# T-FC10W-M.net
KiCad netlist of a schematic drawn in Altium Designer
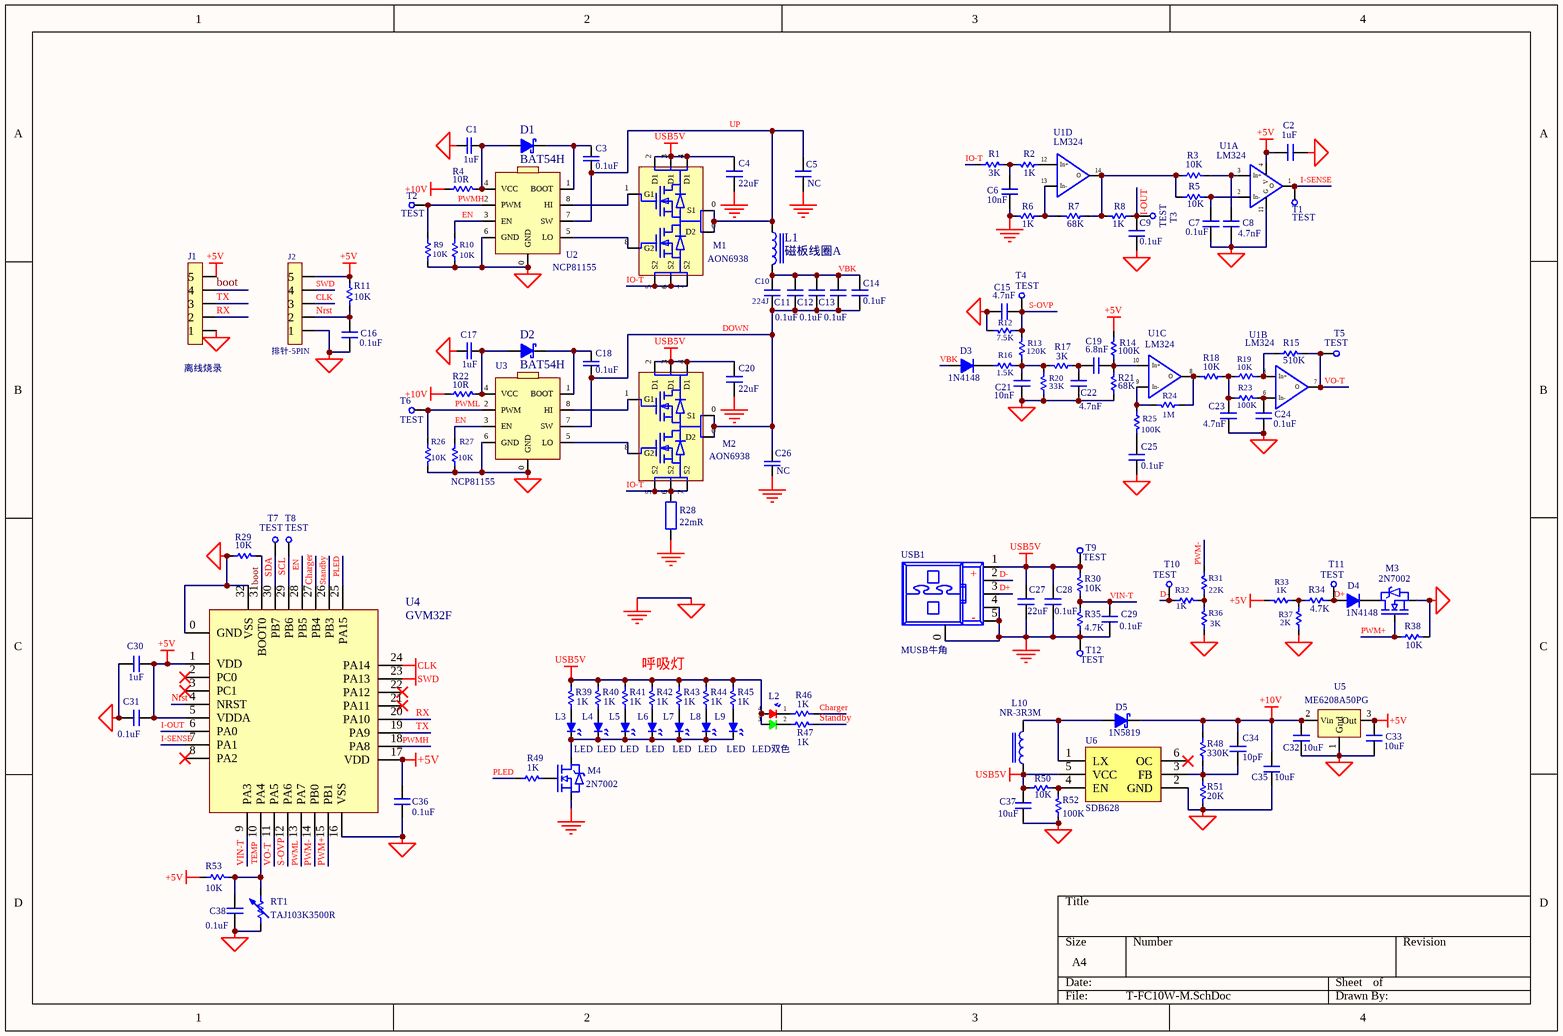
[diagram p0: T-FC10W-M.SchDoc]

(export (version "E")
  (design (tool "Eeschema 10.0.6"))
  (components
    (comp (ref "C1")
      (value "0.1uF")
      (footprint "0603")
      (description "16V")
      (fields (field (name "ALTIUM_UNNAMED_1") "1uF"))
      (libsource (lib "") (part "C0603_1"))
    )
    (comp (ref "C2")
      (value "1uF")
      (footprint "0603")
      (description "16V")
      (libsource (lib "我的元件集成库") (part "C0603"))
    )
    (comp (ref "C3")
      (value "0.1uF")
      (footprint "0603")
      (description "16V")
      (fields (field (name "ALTIUM_UNNAMED_1") "0.1uF"))
      (libsource (lib "") (part "C0603_1"))
    )
    (comp (ref "C4")
      (value "22uF")
      (footprint "1206")
      (description "16V")
      (libsource (lib "我的元件集成库") (part "C1206A"))
    )
    (comp (ref "C5")
      (value "NC")
      (footprint "0603")
      (description "16V")
      (libsource (lib "我的元件集成库") (part "C0603"))
    )
    (comp (ref "C6")
      (value "10nF")
      (footprint "0603")
      (description "16V")
      (libsource (lib "我的元件集成库") (part "C0603"))
    )
    (comp (ref "C7")
      (value "0.1uF")
      (footprint "0603")
      (description "16V")
      (libsource (lib "我的元件集成库") (part "C0603"))
    )
    (comp (ref "C8")
      (value "4.7nF")
      (footprint "0603")
      (description "16V")
      (libsource (lib "我的元件集成库") (part "C0603"))
    )
    (comp (ref "C9")
      (value "0.1uF")
      (footprint "0603")
      (description "16V")
      (libsource (lib "我的元件集成库") (part "C0603"))
    )
    (comp (ref "C10") (value "224J") (footprint "薄膜电容A") (libsource (lib "我的元件集成库") (part "薄膜电容B")))
    (comp (ref "C11")
      (value "0.1uF")
      (footprint "1206")
      (description "NPO")
      (libsource (lib "我的元件集成库") (part "C1206"))
    )
    (comp (ref "C12")
      (value "0.1uF")
      (footprint "1206")
      (description "NPO")
      (libsource (lib "我的元件集成库") (part "C1206"))
    )
    (comp (ref "C13")
      (value "0.1uF")
      (footprint "1206")
      (description "NPO")
      (libsource (lib "我的元件集成库") (part "C1206"))
    )
    (comp (ref "C14")
      (value "0.1uF")
      (footprint "1206")
      (description "NPO")
      (libsource (lib "我的元件集成库") (part "C1206"))
    )
    (comp (ref "C15")
      (value "4.7nF")
      (footprint "0603")
      (description "16V")
      (libsource (lib "我的元件集成库") (part "C0603"))
    )
    (comp (ref "C16")
      (value "0.1uF")
      (footprint "0603")
      (description "16V")
      (libsource (lib "我的元件集成库") (part "C0603"))
    )
    (comp (ref "C17")
      (value "0.1uF")
      (footprint "0603")
      (description "16V")
      (fields (field (name "ALTIUM_UNNAMED_1") "1uF"))
      (libsource (lib "") (part "C0603_1"))
    )
    (comp (ref "C18")
      (value "0.1uF")
      (footprint "0603")
      (description "16V")
      (fields (field (name "ALTIUM_UNNAMED_1") "0.1uF"))
      (libsource (lib "") (part "C0603_1"))
    )
    (comp (ref "C19")
      (value "6.8nF")
      (footprint "0603")
      (description "16V")
      (libsource (lib "我的元件集成库") (part "C0603"))
    )
    (comp (ref "C20")
      (value "22uF")
      (footprint "1206")
      (description "16V")
      (libsource (lib "我的元件集成库") (part "C1206A"))
    )
    (comp (ref "C21")
      (value "10nF")
      (footprint "0603")
      (description "16V")
      (libsource (lib "我的元件集成库") (part "C0603"))
    )
    (comp (ref "C22")
      (value "4.7nF")
      (footprint "0603")
      (description "16V")
      (libsource (lib "我的元件集成库") (part "C0603"))
    )
    (comp (ref "C23")
      (value "4.7nF")
      (footprint "0603")
      (description "16V")
      (libsource (lib "我的元件集成库") (part "C0603"))
    )
    (comp (ref "C24")
      (value "0.1uF")
      (footprint "0603")
      (description "16V")
      (libsource (lib "我的元件集成库") (part "C0603"))
    )
    (comp (ref "C25")
      (value "0.1uF")
      (footprint "0603")
      (description "16V")
      (libsource (lib "我的元件集成库") (part "C0603"))
    )
    (comp (ref "C26")
      (value "NC")
      (footprint "0603")
      (description "16V")
      (libsource (lib "") (part "C0603_1"))
    )
    (comp (ref "C27")
      (value "22uF")
      (footprint "1206")
      (description "16V")
      (libsource (lib "我的元件集成库") (part "C1206A"))
    )
    (comp (ref "C28")
      (value "0.1uF")
      (footprint "0603")
      (description "16V")
      (libsource (lib "我的元件集成库") (part "C0603"))
    )
    (comp (ref "C29")
      (value "0.1uF")
      (footprint "0603")
      (description "16V")
      (libsource (lib "我的元件集成库") (part "C0603"))
    )
    (comp (ref "C30")
      (value "1uF")
      (footprint "0603")
      (description "16V")
      (libsource (lib "我的元件集成库") (part "C0603"))
    )
    (comp (ref "C31")
      (value "0.1uF")
      (footprint "0603")
      (description "16V")
      (libsource (lib "我的元件集成库") (part "C0603"))
    )
    (comp (ref "C32")
      (value "10uF")
      (footprint "0805")
      (description "16V")
      (libsource (lib "我的元件集成库") (part "C0805"))
    )
    (comp (ref "C33")
      (value "10uF")
      (footprint "0805")
      (description "16V")
      (libsource (lib "我的元件集成库") (part "C0805"))
    )
    (comp (ref "C34")
      (value "10pF")
      (footprint "0603")
      (description "16V")
      (libsource (lib "我的元件集成库") (part "C0603"))
    )
    (comp (ref "C35")
      (value "10uF")
      (footprint "0805")
      (description "16V")
      (libsource (lib "我的元件集成库") (part "C0805"))
    )
    (comp (ref "C36")
      (value "0.1uF")
      (footprint "0603")
      (description "16V")
      (libsource (lib "我的元件集成库") (part "C0603"))
    )
    (comp (ref "C37")
      (value "10uF")
      (footprint "0805")
      (description "16V")
      (libsource (lib "我的元件集成库") (part "C0805"))
    )
    (comp (ref "C38")
      (value "0.1uF")
      (footprint "0603")
      (description "16V")
      (libsource (lib "我的元件集成库") (part "C0603"))
    )
    (comp (ref "D1") (value "BAT54H") (footprint "SOD-323") (libsource (lib "我的元件集成库") (part "DIODE-SOD323")))
    (comp (ref "D2") (value "BAT54H") (footprint "SOD-323") (libsource (lib "我的元件集成库") (part "DIODE-SOD323")))
    (comp (ref "D3")
      (value "1N4148")
      (footprint "SOD-323")
      (libsource (lib "我的元件集成库") (part "DIODE-SOD323A"))
    )
    (comp (ref "D4")
      (value "1N4148")
      (footprint "SOD-323")
      (libsource (lib "我的元件集成库") (part "DIODE-SOD323A"))
    )
    (comp (ref "D5") (value "1N5819") (footprint "SOD-123") (libsource (lib "我的元件集成库") (part "DIODE-SOD123")))
    (comp (ref "J1")
      (value "离线烧录")
      (footprint "5PIN排针1.25mm")
      (description "排针-5PIN")
      (libsource (lib "我的元件集成库") (part "排针-5PIN"))
    )
    (comp (ref "J2")
      (value "排针-5PIN")
      (footprint "5PIN排针1.25mm")
      (libsource (lib "我的元件集成库") (part "排针-5PIN"))
    )
    (comp (ref "L1") (value "磁板线圈A") (footprint "磁板线圈") (libsource (lib "我的元件集成库") (part "磁板线圈A")))
    (comp (ref "L2") (value "LED双色") (footprint "LED0603双色") (libsource (lib "我的元件集成库") (part "LED0603双色")))
    (comp (ref "L3")
      (value "LED")
      (footprint "LED0802")
      (description "LED0802侧发光")
      (libsource (lib "我的元件集成库") (part "LED0802"))
    )
    (comp (ref "L4")
      (value "LED")
      (footprint "LED0802")
      (description "LED0802侧发光")
      (libsource (lib "我的元件集成库") (part "LED0802"))
    )
    (comp (ref "L5")
      (value "LED")
      (footprint "LED0802")
      (description "LED0802侧发光")
      (libsource (lib "我的元件集成库") (part "LED0802"))
    )
    (comp (ref "L6")
      (value "LED")
      (footprint "LED0802")
      (description "LED0802侧发光")
      (libsource (lib "我的元件集成库") (part "LED0802"))
    )
    (comp (ref "L7")
      (value "LED")
      (footprint "LED0802")
      (description "LED0802侧发光")
      (libsource (lib "我的元件集成库") (part "LED0802"))
    )
    (comp (ref "L8")
      (value "LED")
      (footprint "LED0802")
      (description "LED0802侧发光")
      (libsource (lib "我的元件集成库") (part "LED0802"))
    )
    (comp (ref "L9")
      (value "LED")
      (footprint "LED0802")
      (description "LED0802侧发光")
      (libsource (lib "我的元件集成库") (part "LED0802"))
    )
    (comp (ref "L10") (value "NR-3R3M") (footprint "L3015T") (libsource (lib "我的元件集成库") (part "L3015")))
    (comp (ref "M1")
      (value "AON6938")
      (footprint "QFN-5*6")
      (description "MOS双N")
      (libsource (lib "我的元件集成库") (part "MOS-双N-DFN56"))
    )
    (comp (ref "M2")
      (value "AON6938")
      (footprint "QFN-5*6")
      (description "MOS双N")
      (libsource (lib "我的元件集成库") (part "MOS-双N-DFN56"))
    )
    (comp (ref "M3")
      (value "2N7002")
      (footprint "SOT-23-L")
      (libsource (lib "我的元件集成库") (part "MOS-N-SOT23A"))
    )
    (comp (ref "M4")
      (value "2N7002")
      (footprint "SOT-23-L")
      (libsource (lib "我的元件集成库") (part "MOS-N-SOT23A"))
    )
    (comp (ref "R1")
      (value "3K")
      (footprint "0603")
      (description "5%")
      (libsource (lib "我的元件集成库") (part "R0603"))
    )
    (comp (ref "R2")
      (value "1K")
      (footprint "0603")
      (description "1%")
      (libsource (lib "我的元件集成库") (part "R0603A"))
    )
    (comp (ref "R3")
      (value "10K")
      (footprint "0603")
      (description "1%")
      (libsource (lib "我的元件集成库") (part "R0603A"))
    )
    (comp (ref "R4")
      (value "10R")
      (footprint "0603")
      (description "5%")
      (libsource (lib "") (part "R0603_1"))
    )
    (comp (ref "R5")
      (value "10K")
      (footprint "0603")
      (description "1%")
      (libsource (lib "我的元件集成库") (part "R0603A"))
    )
    (comp (ref "R6")
      (value "1K")
      (footprint "0603")
      (description "1%")
      (libsource (lib "我的元件集成库") (part "R0603A"))
    )
    (comp (ref "R7")
      (value "68K")
      (footprint "0603")
      (description "1%")
      (libsource (lib "我的元件集成库") (part "R0603A"))
    )
    (comp (ref "R8")
      (value "1K")
      (footprint "0603")
      (description "5%")
      (libsource (lib "我的元件集成库") (part "R0603"))
    )
    (comp (ref "R9")
      (value "10K")
      (footprint "0603")
      (description "5%")
      (libsource (lib "我的元件集成库") (part "R0603"))
    )
    (comp (ref "R10")
      (value "10K")
      (footprint "0603")
      (description "5%")
      (libsource (lib "我的元件集成库") (part "R0603"))
    )
    (comp (ref "R11")
      (value "10K")
      (footprint "0603")
      (description "5%")
      (libsource (lib "我的元件集成库") (part "R0603"))
    )
    (comp (ref "R12")
      (value "7.5K")
      (footprint "0603")
      (description "1%")
      (libsource (lib "我的元件集成库") (part "R0603A"))
    )
    (comp (ref "R13")
      (value "120K")
      (footprint "0603")
      (description "1%")
      (libsource (lib "我的元件集成库") (part "R0603A"))
    )
    (comp (ref "R14")
      (value "100K")
      (footprint "0603")
      (description "1%")
      (libsource (lib "我的元件集成库") (part "R0603A"))
    )
    (comp (ref "R15")
      (value "510K")
      (footprint "0603")
      (description "5%")
      (libsource (lib "我的元件集成库") (part "R0603"))
    )
    (comp (ref "R16")
      (value "1.5K")
      (footprint "0603")
      (description "1%")
      (libsource (lib "我的元件集成库") (part "R0603A"))
    )
    (comp (ref "R17")
      (value "3K")
      (footprint "0603")
      (description "5%")
      (libsource (lib "我的元件集成库") (part "R0603"))
    )
    (comp (ref "R18")
      (value "10K")
      (footprint "0603")
      (description "5%")
      (libsource (lib "我的元件集成库") (part "R0603"))
    )
    (comp (ref "R19")
      (value "10K")
      (footprint "0603")
      (description "1%")
      (libsource (lib "我的元件集成库") (part "R0603A"))
    )
    (comp (ref "R20")
      (value "33K")
      (footprint "0603")
      (description "1%")
      (libsource (lib "我的元件集成库") (part "R0603A"))
    )
    (comp (ref "R21")
      (value "68K")
      (footprint "0603")
      (description "1%")
      (libsource (lib "我的元件集成库") (part "R0603A"))
    )
    (comp (ref "R22")
      (value "10R")
      (footprint "0603")
      (description "5%")
      (libsource (lib "") (part "R0603_1"))
    )
    (comp (ref "R23")
      (value "100K")
      (footprint "0603")
      (description "1%")
      (libsource (lib "我的元件集成库") (part "R0603A"))
    )
    (comp (ref "R24")
      (value "1M")
      (footprint "0603")
      (description "1%")
      (libsource (lib "我的元件集成库") (part "R0603A"))
    )
    (comp (ref "R25")
      (value "100K")
      (footprint "0603")
      (description "1%")
      (libsource (lib "我的元件集成库") (part "R0603A"))
    )
    (comp (ref "R26")
      (value "10K")
      (footprint "0603")
      (description "5%")
      (libsource (lib "我的元件集成库") (part "R0603"))
    )
    (comp (ref "R27")
      (value "10K")
      (footprint "0603")
      (description "5%")
      (libsource (lib "我的元件集成库") (part "R0603"))
    )
    (comp (ref "R28")
      (value "22mR")
      (footprint "1206")
      (description "5%")
      (libsource (lib "我的元件集成库") (part "R1206"))
    )
    (comp (ref "R29")
      (value "10K")
      (footprint "0603")
      (description "5%")
      (libsource (lib "我的元件集成库") (part "R0603"))
    )
    (comp (ref "R30")
      (value "10K")
      (footprint "0603")
      (description "1%")
      (libsource (lib "我的元件集成库") (part "R0603A"))
    )
    (comp (ref "R31")
      (value "22K")
      (footprint "0603")
      (description "1%")
      (libsource (lib "我的元件集成库") (part "R0603A"))
    )
    (comp (ref "R32")
      (value "1K")
      (footprint "0603")
      (description "5%")
      (libsource (lib "我的元件集成库") (part "R0603"))
    )
    (comp (ref "R33")
      (value "1K")
      (footprint "0603")
      (description "1%")
      (libsource (lib "我的元件集成库") (part "R0603A"))
    )
    (comp (ref "R34")
      (value "4.7K")
      (footprint "0603")
      (description "5%")
      (libsource (lib "我的元件集成库") (part "R0603"))
    )
    (comp (ref "R35")
      (value "4.7K")
      (footprint "0603")
      (description "1%")
      (libsource (lib "我的元件集成库") (part "R0603A"))
    )
    (comp (ref "R36")
      (value "3K")
      (footprint "0603")
      (description "1%")
      (libsource (lib "我的元件集成库") (part "R0603A"))
    )
    (comp (ref "R37")
      (value "2K")
      (footprint "0603")
      (description "1%")
      (libsource (lib "我的元件集成库") (part "R0603A"))
    )
    (comp (ref "R38")
      (value "10K")
      (footprint "0603")
      (description "5%")
      (libsource (lib "我的元件集成库") (part "R0603"))
    )
    (comp (ref "R39")
      (value "1K")
      (footprint "0603")
      (description "5%")
      (libsource (lib "我的元件集成库") (part "R0603"))
    )
    (comp (ref "R40")
      (value "1K")
      (footprint "0603")
      (description "5%")
      (libsource (lib "我的元件集成库") (part "R0603"))
    )
    (comp (ref "R41")
      (value "1K")
      (footprint "0603")
      (description "5%")
      (libsource (lib "我的元件集成库") (part "R0603"))
    )
    (comp (ref "R42")
      (value "1K")
      (footprint "0603")
      (description "5%")
      (libsource (lib "我的元件集成库") (part "R0603"))
    )
    (comp (ref "R43")
      (value "1K")
      (footprint "0603")
      (description "5%")
      (libsource (lib "我的元件集成库") (part "R0603"))
    )
    (comp (ref "R44")
      (value "1K")
      (footprint "0603")
      (description "5%")
      (libsource (lib "我的元件集成库") (part "R0603"))
    )
    (comp (ref "R45")
      (value "1K")
      (footprint "0603")
      (description "5%")
      (libsource (lib "我的元件集成库") (part "R0603"))
    )
    (comp (ref "R46")
      (value "1K")
      (footprint "0603")
      (description "5%")
      (libsource (lib "我的元件集成库") (part "R0603"))
    )
    (comp (ref "R47")
      (value "1K")
      (footprint "0603")
      (description "5%")
      (libsource (lib "我的元件集成库") (part "R0603"))
    )
    (comp (ref "R48")
      (value "330K")
      (footprint "0603")
      (description "1%")
      (libsource (lib "我的元件集成库") (part "R0603A"))
    )
    (comp (ref "R49")
      (value "1K")
      (footprint "0603")
      (description "5%")
      (libsource (lib "我的元件集成库") (part "R0603"))
    )
    (comp (ref "R50")
      (value "10K")
      (footprint "0603")
      (description "5%")
      (libsource (lib "我的元件集成库") (part "R0603"))
    )
    (comp (ref "R51")
      (value "20K")
      (footprint "0603")
      (description "1%")
      (libsource (lib "我的元件集成库") (part "R0603A"))
    )
    (comp (ref "R52")
      (value "100K")
      (footprint "0603")
      (description "5%")
      (libsource (lib "我的元件集成库") (part "R0603"))
    )
    (comp (ref "R53")
      (value "10K")
      (footprint "0603")
      (description "5%")
      (libsource (lib "我的元件集成库") (part "R0603"))
    )
    (comp (ref "RT1")
      (value "TAJ103K3500R")
      (footprint "0603")
      (description "5%")
      (libsource (lib "我的元件集成库") (part "R0603-ADJ"))
    )
    (comp (ref "T1") (value "TEST") (footprint "测试点") (libsource (lib "我的元件集成库") (part "TEST-PIONT")))
    (comp (ref "T2") (value "TEST") (footprint "测试点") (libsource (lib "我的元件集成库") (part "TEST-PIONT")))
    (comp (ref "T3") (value "TEST") (footprint "测试点") (libsource (lib "我的元件集成库") (part "TEST-PIONT")))
    (comp (ref "T4") (value "TEST") (footprint "测试点") (libsource (lib "我的元件集成库") (part "TEST-PIONT")))
    (comp (ref "T5") (value "TEST") (footprint "测试点") (libsource (lib "我的元件集成库") (part "TEST-PIONT")))
    (comp (ref "T6") (value "TEST") (footprint "测试点") (libsource (lib "我的元件集成库") (part "TEST-PIONT")))
    (comp (ref "T7") (value "TEST") (footprint "测试点") (libsource (lib "我的元件集成库") (part "TEST-PIONT")))
    (comp (ref "T8") (value "TEST") (footprint "测试点") (libsource (lib "我的元件集成库") (part "TEST-PIONT")))
    (comp (ref "T9") (value "TEST") (footprint "测试点") (libsource (lib "我的元件集成库") (part "TEST-PIONT")))
    (comp (ref "T10") (value "TEST") (footprint "测试点") (libsource (lib "我的元件集成库") (part "TEST-PIONT")))
    (comp (ref "T11") (value "TEST") (footprint "测试点") (libsource (lib "我的元件集成库") (part "TEST-PIONT")))
    (comp (ref "T12") (value "TEST") (footprint "测试点") (libsource (lib "我的元件集成库") (part "TEST-PIONT")))
    (comp (ref "U1") (value "LM324") (footprint "SOP-14") (libsource (lib "我的元件集成库") (part "IC-SOP-14")))
    (comp (ref "U2") (value "NCP81155") (footprint "QFN-3*3-1") (libsource (lib "我的元件集成库") (part "IC-QFN33")))
    (comp (ref "U3") (value "NCP81155") (footprint "QFN-3*3-1") (libsource (lib "我的元件集成库") (part "IC-QFN33")))
    (comp (ref "U4") (value "GVM32F") (footprint "QFN-32PIN") (libsource (lib "我的元件集成库") (part "IC-QFN32PA")))
    (comp (ref "U5")
      (value "ME6208A50PG")
      (footprint "SOT-89")
      (libsource (lib "我的元件集成库") (part "LDO-SOT89"))
    )
    (comp (ref "U6") (value "SDB628") (footprint "SOT-23-6") (libsource (lib "我的元件集成库") (part "IC-SOT23-6")))
    (comp (ref "USB1")
      (value "MUSB牛角")
      (footprint "MICRO-USB牛角")
      (libsource (lib "我的元件集成库") (part "MICRO-USB-牛角"))
    )
  )
  (nets
    (net (code "1") (name "+5V") (class "Default")
      (node (ref "C2") (pin "2") (pinfunction "2_2") (pintype "passive"))
      (node (ref "C30") (pin "1") (pinfunction "1_1") (pintype "passive"))
      (node (ref "C31") (pin "1") (pinfunction "1_1") (pintype "passive"))
      (node (ref "C33") (pin "2") (pinfunction "2_2") (pintype "passive"))
      (node (ref "C36") (pin "1") (pinfunction "1_1") (pintype "passive"))
      (node (ref "J1") (pin "5") (pinfunction "5_5") (pintype "passive"))
      (node (ref "J2") (pin "5") (pinfunction "5_5") (pintype "passive"))
      (node (ref "R11") (pin "1") (pinfunction "1_1") (pintype "passive"))
      (node (ref "R14") (pin "2") (pinfunction "2_2") (pintype "passive"))
      (node (ref "R33") (pin "2") (pinfunction "2_2") (pintype "passive"))
      (node (ref "R53") (pin "1") (pinfunction "1_1") (pintype "passive"))
      (node (ref "U1") (pin "4") (pinfunction "V_4") (pintype "passive"))
      (node (ref "U4") (pin "1") (pinfunction "VDD_1") (pintype "passive"))
      (node (ref "U4") (pin "17") (pinfunction "VDD_17") (pintype "passive"))
      (node (ref "U4") (pin "5") (pinfunction "VDDA_5") (pintype "passive"))
      (node (ref "U5") (pin "3") (pinfunction "Out_3") (pintype "passive"))
    )
    (net (code "2") (name "+10V") (class "Default")
      (node (ref "C32") (pin "2") (pinfunction "2_2") (pintype "passive"))
      (node (ref "C34") (pin "2") (pinfunction "2_2") (pintype "passive"))
      (node (ref "C35") (pin "2") (pinfunction "2_2") (pintype "passive"))
      (node (ref "D5") (pin "2") (pinfunction "K_2") (pintype "passive"))
      (node (ref "R22") (pin "1") (pinfunction "1_1") (pintype "passive"))
      (node (ref "R4") (pin "1") (pinfunction "1_1") (pintype "passive"))
      (node (ref "R48") (pin "2") (pinfunction "2_2") (pintype "passive"))
      (node (ref "U5") (pin "2") (pinfunction "Vin_2") (pintype "passive"))
    )
    (net (code "3") (name "/Charger") (class "Default")
      (node (ref "R46") (pin "2") (pinfunction "2_2") (pintype "passive"))
      (node (ref "U4") (pin "27") (pinfunction "PB4_27") (pintype "passive"))
    )
    (net (code "4") (name "/D+") (class "Default")
      (node (ref "D4") (pin "1") (pinfunction "1_1") (pintype "passive"))
      (node (ref "R34") (pin "2") (pinfunction "2_2") (pintype "passive"))
      (node (ref "T11") (pin "1") (pinfunction "1_1") (pintype "passive"))
      (node (ref "USB1") (pin "3") (pinfunction "3_3") (pintype "passive"))
    )
    (net (code "5") (name "/D-") (class "Default")
      (node (ref "R32") (pin "1") (pinfunction "1_1") (pintype "passive"))
      (node (ref "T10") (pin "1") (pinfunction "1_1") (pintype "passive"))
      (node (ref "USB1") (pin "2") (pinfunction "2_2") (pintype "passive"))
    )
    (net (code "6") (name "/DOWN") (class "Default")
      (node (ref "C10") (pin "1") (pinfunction "1_1") (pintype "passive"))
      (node (ref "C11") (pin "1") (pinfunction "1_1") (pintype "passive"))
      (node (ref "C12") (pin "1") (pinfunction "1_1") (pintype "passive"))
      (node (ref "C13") (pin "1") (pinfunction "1_1") (pintype "passive"))
      (node (ref "C14") (pin "1") (pinfunction "1_1") (pintype "passive"))
      (node (ref "C18") (pin "1") (pinfunction "1_1") (pintype "passive"))
      (node (ref "C26") (pin "2") (pinfunction "2_2") (pintype "passive"))
      (node (ref "M2") (pin "0") (pinfunction "S1_0") (pintype "passive"))
      (node (ref "U3") (pin "7") (pinfunction "SW_7") (pintype "passive"))
    )
    (net (code "7") (name "/EN") (class "Default")
      (node (ref "R10") (pin "2") (pinfunction "2_2") (pintype "passive"))
      (node (ref "R27") (pin "2") (pinfunction "2_2") (pintype "passive"))
      (node (ref "U2") (pin "3") (pinfunction "EN_3") (pintype "passive"))
      (node (ref "U3") (pin "3") (pinfunction "EN_3") (pintype "passive"))
      (node (ref "U4") (pin "28") (pinfunction "PB5_28") (pintype "passive"))
    )
    (net (code "8") (name "/I-OUT") (class "Default")
      (node (ref "C9") (pin "1") (pinfunction "1_1") (pintype "passive"))
      (node (ref "R8") (pin "1") (pinfunction "1_1") (pintype "passive"))
      (node (ref "T3") (pin "1") (pinfunction "1_1") (pintype "passive"))
      (node (ref "U4") (pin "6") (pinfunction "PA0_6") (pintype "passive"))
    )
    (net (code "9") (name "/I-SENSE") (class "Default")
      (node (ref "T1") (pin "1") (pinfunction "1_1") (pintype "passive"))
      (node (ref "U1") (pin "1") (pinfunction "O_1") (pintype "passive"))
      (node (ref "U4") (pin "7") (pinfunction "PA1_7") (pintype "passive"))
    )
    (net (code "10") (name "/IO-T") (class "Default")
      (node (ref "M1") (pin "5") (pinfunction "S2_5") (pintype "passive"))
      (node (ref "M1") (pin "6") (pinfunction "S2_6") (pintype "passive"))
      (node (ref "M1") (pin "7") (pinfunction "S2_7") (pintype "passive"))
      (node (ref "M2") (pin "5") (pinfunction "S2_5") (pintype "passive"))
      (node (ref "M2") (pin "6") (pinfunction "S2_6") (pintype "passive"))
      (node (ref "M2") (pin "7") (pinfunction "S2_7") (pintype "passive"))
      (node (ref "R1") (pin "1") (pinfunction "1_1") (pintype "passive"))
      (node (ref "R28") (pin "2") (pinfunction "2_2") (pintype "passive"))
    )
    (net (code "11") (name "/Nrst") (class "Default")
      (node (ref "C16") (pin "2") (pinfunction "2_2") (pintype "passive"))
      (node (ref "J2") (pin "2") (pinfunction "2_2") (pintype "passive"))
      (node (ref "R11") (pin "2") (pinfunction "2_2") (pintype "passive"))
      (node (ref "U4") (pin "4") (pinfunction "NRST_4") (pintype "passive"))
    )
    (net (code "12") (name "/PLED") (class "Default")
      (node (ref "R49") (pin "1") (pinfunction "1_1") (pintype "passive"))
      (node (ref "U4") (pin "25") (pinfunction "PA15_25") (pintype "passive"))
    )
    (net (code "13") (name "/PWM+") (class "Default")
      (node (ref "M3") (pin "1") (pinfunction "G_1") (pintype "power_in"))
      (node (ref "R38") (pin "1") (pinfunction "1_1") (pintype "passive"))
      (node (ref "U4") (pin "15") (pinfunction "PB1_15") (pintype "passive"))
    )
    (net (code "14") (name "/PWM-") (class "Default")
      (node (ref "R31") (pin "2") (pinfunction "2_2") (pintype "passive"))
      (node (ref "U4") (pin "14") (pinfunction "PB0_14") (pintype "passive"))
    )
    (net (code "15") (name "/PWMH") (class "Default")
      (node (ref "R9") (pin "1") (pinfunction "1_1") (pintype "passive"))
      (node (ref "T2") (pin "1") (pinfunction "1_1") (pintype "passive"))
      (node (ref "U2") (pin "2") (pinfunction "PWM_2") (pintype "passive"))
      (node (ref "U4") (pin "18") (pinfunction "PA8_18") (pintype "passive"))
    )
    (net (code "16") (name "/PWML") (class "Default")
      (node (ref "R26") (pin "1") (pinfunction "1_1") (pintype "passive"))
      (node (ref "T6") (pin "1") (pinfunction "1_1") (pintype "passive"))
      (node (ref "U3") (pin "2") (pinfunction "PWM_2") (pintype "passive"))
      (node (ref "U4") (pin "13") (pinfunction "PA7_13") (pintype "passive"))
    )
    (net (code "17") (name "/RX") (class "Default")
      (node (ref "J1") (pin "2") (pinfunction "2_2") (pintype "passive"))
      (node (ref "U4") (pin "20") (pinfunction "PA10_20") (pintype "passive"))
    )
    (net (code "18") (name "/S-OVP") (class "Default")
      (node (ref "C15") (pin "1") (pinfunction "1_1") (pintype "passive"))
      (node (ref "R12") (pin "1") (pinfunction "1_1") (pintype "passive"))
      (node (ref "R13") (pin "2") (pinfunction "2_2") (pintype "passive"))
      (node (ref "T4") (pin "1") (pinfunction "1_1") (pintype "passive"))
      (node (ref "U4") (pin "12") (pinfunction "PA6_12") (pintype "passive"))
    )
    (net (code "19") (name "/SCL") (class "Default")
      (node (ref "T8") (pin "1") (pinfunction "1_1") (pintype "passive"))
      (node (ref "U4") (pin "29") (pinfunction "PB6_29") (pintype "passive"))
    )
    (net (code "20") (name "/SDA") (class "Default")
      (node (ref "T7") (pin "1") (pinfunction "1_1") (pintype "passive"))
      (node (ref "U4") (pin "30") (pinfunction "PB7_30") (pintype "passive"))
    )
    (net (code "21") (name "/Standby") (class "Default")
      (node (ref "R47") (pin "2") (pinfunction "2_2") (pintype "passive"))
      (node (ref "U4") (pin "26") (pinfunction "PB3_26") (pintype "passive"))
    )
    (net (code "22") (name "/TEMP") (class "Default")
      (node (ref "C38") (pin "2") (pinfunction "2_2") (pintype "passive"))
      (node (ref "R53") (pin "2") (pinfunction "2_2") (pintype "passive"))
      (node (ref "RT1") (pin "2") (pinfunction "2_2") (pintype "passive"))
      (node (ref "U4") (pin "10") (pinfunction "PA4_10") (pintype "passive"))
    )
    (net (code "23") (name "/TX") (class "Default")
      (node (ref "J1") (pin "3") (pinfunction "3_3") (pintype "passive"))
      (node (ref "U4") (pin "19") (pinfunction "PA9_19") (pintype "passive"))
    )
    (net (code "24") (name "/UP") (class "Default")
      (node (ref "C3") (pin "1") (pinfunction "1_1") (pintype "passive"))
      (node (ref "C5") (pin "2") (pinfunction "2_2") (pintype "passive"))
      (node (ref "L1") (pin "1") (pinfunction "1_1") (pintype "passive"))
      (node (ref "M1") (pin "0") (pinfunction "S1_0") (pintype "passive"))
      (node (ref "U2") (pin "7") (pinfunction "SW_7") (pintype "passive"))
    )
    (net (code "25") (name "/VBK") (class "Default")
      (node (ref "C10") (pin "2") (pinfunction "2_2") (pintype "passive"))
      (node (ref "C11") (pin "2") (pinfunction "2_2") (pintype "passive"))
      (node (ref "C12") (pin "2") (pinfunction "2_2") (pintype "passive"))
      (node (ref "C13") (pin "2") (pinfunction "2_2") (pintype "passive"))
      (node (ref "C14") (pin "2") (pinfunction "2_2") (pintype "passive"))
      (node (ref "D3") (pin "1") (pinfunction "1_1") (pintype "passive"))
      (node (ref "L1") (pin "2") (pinfunction "2_2") (pintype "passive"))
    )
    (net (code "26") (name "/VIN-T") (class "Default")
      (node (ref "C29") (pin "2") (pinfunction "2_2") (pintype "passive"))
      (node (ref "R30") (pin "1") (pinfunction "1_1") (pintype "passive"))
      (node (ref "R35") (pin "2") (pinfunction "2_2") (pintype "passive"))
      (node (ref "U4") (pin "9") (pinfunction "PA3_9") (pintype "passive"))
    )
    (net (code "27") (name "/VO-T") (class "Default")
      (node (ref "R15") (pin "2") (pinfunction "2_2") (pintype "passive"))
      (node (ref "T5") (pin "1") (pinfunction "1_1") (pintype "passive"))
      (node (ref "U1") (pin "7") (pinfunction "O_7") (pintype "passive"))
      (node (ref "U4") (pin "11") (pinfunction "PA5_11") (pintype "passive"))
    )
    (net (code "28") (name "/boot") (class "Default")
      (node (ref "J1") (pin "4") (pinfunction "4_4") (pintype "passive"))
      (node (ref "R29") (pin "2") (pinfunction "2_2") (pintype "passive"))
      (node (ref "U4") (pin "31") (pinfunction "BOOT0_31") (pintype "passive"))
    )
    (net (code "29") (name "CLK") (class "Default")
      (node (ref "J2") (pin "3") (pinfunction "3_3") (pintype "passive"))
      (node (ref "U4") (pin "24") (pinfunction "PA14_24") (pintype "passive"))
    )
    (net (code "30") (name "GND") (class "Default")
      (node (ref "C1") (pin "2") (pinfunction "2_2") (pintype "passive"))
      (node (ref "C15") (pin "2") (pinfunction "2_2") (pintype "passive"))
      (node (ref "C16") (pin "1") (pinfunction "1_1") (pintype "passive"))
      (node (ref "C17") (pin "2") (pinfunction "2_2") (pintype "passive"))
      (node (ref "C2") (pin "1") (pinfunction "1_1") (pintype "passive"))
      (node (ref "C20") (pin "1") (pinfunction "1_1") (pintype "passive"))
      (node (ref "C21") (pin "1") (pinfunction "1_1") (pintype "passive"))
      (node (ref "C22") (pin "1") (pinfunction "1_1") (pintype "passive"))
      (node (ref "C23") (pin "1") (pinfunction "1_1") (pintype "passive"))
      (node (ref "C24") (pin "1") (pinfunction "1_1") (pintype "passive"))
      (node (ref "C25") (pin "2") (pinfunction "2_2") (pintype "passive"))
      (node (ref "C26") (pin "1") (pinfunction "1_1") (pintype "passive"))
      (node (ref "C27") (pin "1") (pinfunction "1_1") (pintype "passive"))
      (node (ref "C28") (pin "1") (pinfunction "1_1") (pintype "passive"))
      (node (ref "C29") (pin "1") (pinfunction "1_1") (pintype "passive"))
      (node (ref "C30") (pin "2") (pinfunction "2_2") (pintype "passive"))
      (node (ref "C31") (pin "2") (pinfunction "2_2") (pintype "passive"))
      (node (ref "C32") (pin "1") (pinfunction "1_1") (pintype "passive"))
      (node (ref "C33") (pin "1") (pinfunction "1_1") (pintype "passive"))
      (node (ref "C35") (pin "1") (pinfunction "1_1") (pintype "passive"))
      (node (ref "C36") (pin "2") (pinfunction "2_2") (pintype "passive"))
      (node (ref "C37") (pin "1") (pinfunction "1_1") (pintype "passive"))
      (node (ref "C38") (pin "1") (pinfunction "1_1") (pintype "passive"))
      (node (ref "C4") (pin "1") (pinfunction "1_1") (pintype "passive"))
      (node (ref "C5") (pin "1") (pinfunction "1_1") (pintype "passive"))
      (node (ref "C6") (pin "1") (pinfunction "1_1") (pintype "passive"))
      (node (ref "C7") (pin "1") (pinfunction "1_1") (pintype "passive"))
      (node (ref "C8") (pin "1") (pinfunction "1_1") (pintype "passive"))
      (node (ref "C9") (pin "2") (pinfunction "2_2") (pintype "passive"))
      (node (ref "J1") (pin "1") (pinfunction "1_1") (pintype "passive"))
      (node (ref "J2") (pin "1") (pinfunction "1_1") (pintype "passive"))
      (node (ref "M3") (pin "3") (pinfunction "S_3") (pintype "power_in"))
      (node (ref "M4") (pin "3") (pinfunction "S_3") (pintype "power_in"))
      (node (ref "R10") (pin "1") (pinfunction "1_1") (pintype "passive"))
      (node (ref "R12") (pin "2") (pinfunction "2_2") (pintype "passive"))
      (node (ref "R20") (pin "1") (pinfunction "1_1") (pintype "passive"))
      (node (ref "R21") (pin "1") (pinfunction "1_1") (pintype "passive"))
      (node (ref "R26") (pin "2") (pinfunction "2_2") (pintype "passive"))
      (node (ref "R27") (pin "1") (pinfunction "1_1") (pintype "passive"))
      (node (ref "R28") (pin "1") (pinfunction "1_1") (pintype "passive"))
      (node (ref "R29") (pin "1") (pinfunction "1_1") (pintype "passive"))
      (node (ref "R35") (pin "1") (pinfunction "1_1") (pintype "passive"))
      (node (ref "R36") (pin "1") (pinfunction "1_1") (pintype "passive"))
      (node (ref "R37") (pin "1") (pinfunction "1_1") (pintype "passive"))
      (node (ref "R38") (pin "2") (pinfunction "2_2") (pintype "passive"))
      (node (ref "R51") (pin "2") (pinfunction "2_2") (pintype "passive"))
      (node (ref "R52") (pin "1") (pinfunction "1_1") (pintype "passive"))
      (node (ref "R6") (pin "2") (pinfunction "2_2") (pintype "passive"))
      (node (ref "R9") (pin "2") (pinfunction "2_2") (pintype "passive"))
      (node (ref "RT1") (pin "1") (pinfunction "1_1") (pintype "passive"))
      (node (ref "T12") (pin "1") (pinfunction "1_1") (pintype "passive"))
      (node (ref "U1") (pin "11") (pinfunction "G_11") (pintype "passive"))
      (node (ref "U2") (pin "0") (pinfunction "GND_0") (pintype "passive"))
      (node (ref "U2") (pin "6") (pinfunction "GND_6") (pintype "passive"))
      (node (ref "U3") (pin "0") (pinfunction "GND_0") (pintype "passive"))
      (node (ref "U3") (pin "6") (pinfunction "GND_6") (pintype "passive"))
      (node (ref "U4") (pin "0") (pinfunction "GND_0") (pintype "passive"))
      (node (ref "U4") (pin "16") (pinfunction "VSS_16") (pintype "passive"))
      (node (ref "U4") (pin "32") (pinfunction "VSS_32") (pintype "passive"))
      (node (ref "U5") (pin "1") (pinfunction "Gnd_1") (pintype "passive"))
      (node (ref "U6") (pin "2") (pinfunction "GND_2") (pintype "passive"))
      (node (ref "USB1") (pin "0") (pinfunction "0_0") (pintype "passive"))
      (node (ref "USB1") (pin "4") (pinfunction "4_4") (pintype "passive"))
      (node (ref "USB1") (pin "5") (pinfunction "5_5") (pintype "passive"))
    )
    (net (code "31") (name "Net-(C6-Pad2)") (class "Default")
      (node (ref "C6") (pin "2") (pinfunction "2_2") (pintype "passive"))
      (node (ref "R1") (pin "2") (pinfunction "2_2") (pintype "passive"))
      (node (ref "R2") (pin "2") (pinfunction "2_2") (pintype "passive"))
    )
    (net (code "32") (name "Net-(C19-Pad1)") (class "Default")
      (node (ref "C19") (pin "1") (pinfunction "1_1") (pintype "passive"))
      (node (ref "C22") (pin "2") (pinfunction "2_2") (pintype "passive"))
      (node (ref "R17") (pin "1") (pinfunction "1_1") (pintype "passive"))
    )
    (net (code "33") (name "Net-(C21-Pad2)") (class "Default")
      (node (ref "C21") (pin "2") (pinfunction "2_2") (pintype "passive"))
      (node (ref "R13") (pin "1") (pinfunction "1_1") (pintype "passive"))
      (node (ref "R16") (pin "2") (pinfunction "2_2") (pintype "passive"))
      (node (ref "R17") (pin "2") (pinfunction "2_2") (pintype "passive"))
      (node (ref "R20") (pin "2") (pinfunction "2_2") (pintype "passive"))
    )
    (net (code "34") (name "Net-(C23-Pad2)") (class "Default")
      (node (ref "C23") (pin "2") (pinfunction "2_2") (pintype "passive"))
      (node (ref "R18") (pin "1") (pinfunction "1_1") (pintype "passive"))
      (node (ref "R19") (pin "1") (pinfunction "1_1") (pintype "passive"))
      (node (ref "R23") (pin "1") (pinfunction "1_1") (pintype "passive"))
    )
    (net (code "35") (name "Net-(C25-Pad1)") (class "Default")
      (node (ref "C25") (pin "1") (pinfunction "1_1") (pintype "passive"))
      (node (ref "R25") (pin "2") (pinfunction "2_2") (pintype "passive"))
    )
    (net (code "36") (name "Net-(D1-A)") (class "Default")
      (node (ref "C1") (pin "1") (pinfunction "1_1") (pintype "passive"))
      (node (ref "D1") (pin "1") (pinfunction "A_1") (pintype "passive"))
      (node (ref "R4") (pin "2") (pinfunction "2_2") (pintype "passive"))
      (node (ref "U2") (pin "4") (pinfunction "VCC_4") (pintype "passive"))
    )
    (net (code "37") (name "Net-(D1-K)") (class "Default")
      (node (ref "C3") (pin "2") (pinfunction "2_2") (pintype "passive"))
      (node (ref "D1") (pin "2") (pinfunction "K_2") (pintype "passive"))
      (node (ref "U2") (pin "1") (pinfunction "BOOT_1") (pintype "passive"))
    )
    (net (code "38") (name "Net-(D2-A)") (class "Default")
      (node (ref "C17") (pin "1") (pinfunction "1_1") (pintype "passive"))
      (node (ref "D2") (pin "1") (pinfunction "A_1") (pintype "passive"))
      (node (ref "R22") (pin "2") (pinfunction "2_2") (pintype "passive"))
      (node (ref "U3") (pin "4") (pinfunction "VCC_4") (pintype "passive"))
    )
    (net (code "39") (name "Net-(D2-K)") (class "Default")
      (node (ref "C18") (pin "2") (pinfunction "2_2") (pintype "passive"))
      (node (ref "D2") (pin "2") (pinfunction "K_2") (pintype "passive"))
      (node (ref "U3") (pin "1") (pinfunction "BOOT_1") (pintype "passive"))
    )
    (net (code "40") (name "Net-(D3-Pad2)") (class "Default")
      (node (ref "D3") (pin "2") (pinfunction "2_2") (pintype "passive"))
      (node (ref "R16") (pin "1") (pinfunction "1_1") (pintype "passive"))
    )
    (net (code "41") (name "Net-(D5-A)") (class "Default")
      (node (ref "D5") (pin "1") (pinfunction "A_1") (pintype "passive"))
      (node (ref "L10") (pin "2") (pinfunction "2_2") (pintype "passive"))
      (node (ref "U6") (pin "1") (pinfunction "LX_1") (pintype "passive"))
    )
    (net (code "42") (name "Net-(L2-G)") (class "Default")
      (node (ref "L2") (pin "2") (pinfunction "G_2") (pintype "passive"))
      (node (ref "R47") (pin "1") (pinfunction "1_1") (pintype "passive"))
    )
    (net (code "43") (name "Net-(L2-R)") (class "Default")
      (node (ref "L2") (pin "1") (pinfunction "R_1") (pintype "passive"))
      (node (ref "R46") (pin "1") (pinfunction "1_1") (pintype "passive"))
    )
    (net (code "44") (name "Net-(L3-A)") (class "Default")
      (node (ref "L3") (pin "1") (pinfunction "A_1") (pintype "passive"))
      (node (ref "R39") (pin "1") (pinfunction "1_1") (pintype "passive"))
    )
    (net (code "45") (name "Net-(L3-K)") (class "Default")
      (node (ref "L3") (pin "2") (pinfunction "K_2") (pintype "passive"))
      (node (ref "L4") (pin "2") (pinfunction "K_2") (pintype "passive"))
      (node (ref "L5") (pin "2") (pinfunction "K_2") (pintype "passive"))
      (node (ref "L6") (pin "2") (pinfunction "K_2") (pintype "passive"))
      (node (ref "L7") (pin "2") (pinfunction "K_2") (pintype "passive"))
      (node (ref "L8") (pin "2") (pinfunction "K_2") (pintype "passive"))
      (node (ref "L9") (pin "2") (pinfunction "K_2") (pintype "passive"))
      (node (ref "M4") (pin "2") (pinfunction "D_2") (pintype "power_in"))
    )
    (net (code "46") (name "Net-(L4-A)") (class "Default")
      (node (ref "L4") (pin "1") (pinfunction "A_1") (pintype "passive"))
      (node (ref "R40") (pin "1") (pinfunction "1_1") (pintype "passive"))
    )
    (net (code "47") (name "Net-(L5-A)") (class "Default")
      (node (ref "L5") (pin "1") (pinfunction "A_1") (pintype "passive"))
      (node (ref "R41") (pin "1") (pinfunction "1_1") (pintype "passive"))
    )
    (net (code "48") (name "Net-(L6-A)") (class "Default")
      (node (ref "L6") (pin "1") (pinfunction "A_1") (pintype "passive"))
      (node (ref "R42") (pin "1") (pinfunction "1_1") (pintype "passive"))
    )
    (net (code "49") (name "Net-(L7-A)") (class "Default")
      (node (ref "L7") (pin "1") (pinfunction "A_1") (pintype "passive"))
      (node (ref "R43") (pin "1") (pinfunction "1_1") (pintype "passive"))
    )
    (net (code "50") (name "Net-(L8-A)") (class "Default")
      (node (ref "L8") (pin "1") (pinfunction "A_1") (pintype "passive"))
      (node (ref "R44") (pin "1") (pinfunction "1_1") (pintype "passive"))
    )
    (net (code "51") (name "Net-(L9-A)") (class "Default")
      (node (ref "L9") (pin "1") (pinfunction "A_1") (pintype "passive"))
      (node (ref "R45") (pin "1") (pinfunction "1_1") (pintype "passive"))
    )
    (net (code "52") (name "Net-(M1-G1)") (class "Default")
      (node (ref "M1") (pin "1") (pinfunction "G1_1") (pintype "passive"))
      (node (ref "U2") (pin "8") (pinfunction "HI_8") (pintype "passive"))
    )
    (net (code "53") (name "Net-(M1-G2)") (class "Default")
      (node (ref "M1") (pin "8") (pinfunction "G2_8") (pintype "passive"))
      (node (ref "U2") (pin "5") (pinfunction "LO_5") (pintype "passive"))
    )
    (net (code "54") (name "Net-(M2-G1)") (class "Default")
      (node (ref "M2") (pin "1") (pinfunction "G1_1") (pintype "passive"))
      (node (ref "U3") (pin "8") (pinfunction "HI_8") (pintype "passive"))
    )
    (net (code "55") (name "Net-(M2-G2)") (class "Default")
      (node (ref "M2") (pin "8") (pinfunction "G2_8") (pintype "passive"))
      (node (ref "U3") (pin "5") (pinfunction "LO_5") (pintype "passive"))
    )
    (net (code "56") (name "Net-(M3-D)") (class "Default")
      (node (ref "D4") (pin "2") (pinfunction "2_2") (pintype "passive"))
      (node (ref "M3") (pin "2") (pinfunction "D_2") (pintype "power_in"))
    )
    (net (code "57") (name "Net-(M4-G)") (class "Default")
      (node (ref "M4") (pin "1") (pinfunction "G_1") (pintype "power_in"))
      (node (ref "R49") (pin "2") (pinfunction "2_2") (pintype "passive"))
    )
    (net (code "58") (name "Net-(R31-Pad1)") (class "Default")
      (node (ref "R31") (pin "1") (pinfunction "1_1") (pintype "passive"))
      (node (ref "R32") (pin "2") (pinfunction "2_2") (pintype "passive"))
      (node (ref "R36") (pin "2") (pinfunction "2_2") (pintype "passive"))
    )
    (net (code "59") (name "Net-(R33-Pad1)") (class "Default")
      (node (ref "R33") (pin "1") (pinfunction "1_1") (pintype "passive"))
      (node (ref "R34") (pin "1") (pinfunction "1_1") (pintype "passive"))
      (node (ref "R37") (pin "2") (pinfunction "2_2") (pintype "passive"))
    )
    (net (code "60") (name "Net-(U1A-In+)") (class "Default")
      (node (ref "C8") (pin "2") (pinfunction "2_2") (pintype "passive"))
      (node (ref "R3") (pin "2") (pinfunction "2_2") (pintype "passive"))
      (node (ref "U1") (pin "3") (pinfunction "In+_3") (pintype "passive"))
    )
    (net (code "61") (name "Net-(U1A-In-)") (class "Default")
      (node (ref "C7") (pin "2") (pinfunction "2_2") (pintype "passive"))
      (node (ref "R5") (pin "2") (pinfunction "2_2") (pintype "passive"))
      (node (ref "U1") (pin "2") (pinfunction "In-_2") (pintype "passive"))
    )
    (net (code "62") (name "Net-(U1B-In+)") (class "Default")
      (node (ref "R15") (pin "1") (pinfunction "1_1") (pintype "passive"))
      (node (ref "R19") (pin "2") (pinfunction "2_2") (pintype "passive"))
      (node (ref "U1") (pin "5") (pinfunction "In+_5") (pintype "passive"))
    )
    (net (code "63") (name "Net-(U1B-In-)") (class "Default")
      (node (ref "C24") (pin "2") (pinfunction "2_2") (pintype "passive"))
      (node (ref "R23") (pin "2") (pinfunction "2_2") (pintype "passive"))
      (node (ref "U1") (pin "6") (pinfunction "In-_6") (pintype "passive"))
    )
    (net (code "64") (name "Net-(U1C-In+)") (class "Default")
      (node (ref "C19") (pin "2") (pinfunction "2_2") (pintype "passive"))
      (node (ref "R14") (pin "1") (pinfunction "1_1") (pintype "passive"))
      (node (ref "R21") (pin "2") (pinfunction "2_2") (pintype "passive"))
      (node (ref "U1") (pin "10") (pinfunction "In+_10") (pintype "passive"))
    )
    (net (code "65") (name "Net-(U1C-In-)") (class "Default")
      (node (ref "R24") (pin "2") (pinfunction "2_2") (pintype "passive"))
      (node (ref "R25") (pin "1") (pinfunction "1_1") (pintype "passive"))
      (node (ref "U1") (pin "9") (pinfunction "In-_9") (pintype "passive"))
    )
    (net (code "66") (name "Net-(U1C-O)") (class "Default")
      (node (ref "R18") (pin "2") (pinfunction "2_2") (pintype "passive"))
      (node (ref "R24") (pin "1") (pinfunction "1_1") (pintype "passive"))
      (node (ref "U1") (pin "8") (pinfunction "O_8") (pintype "passive"))
    )
    (net (code "67") (name "Net-(U1D-In+)") (class "Default")
      (node (ref "R2") (pin "1") (pinfunction "1_1") (pintype "passive"))
      (node (ref "U1") (pin "12") (pinfunction "In+_12") (pintype "passive"))
    )
    (net (code "68") (name "Net-(U1D-In-)") (class "Default")
      (node (ref "R6") (pin "1") (pinfunction "1_1") (pintype "passive"))
      (node (ref "R7") (pin "2") (pinfunction "2_2") (pintype "passive"))
      (node (ref "U1") (pin "13") (pinfunction "In-_13") (pintype "passive"))
    )
    (net (code "69") (name "Net-(U1D-O)") (class "Default")
      (node (ref "R3") (pin "1") (pinfunction "1_1") (pintype "passive"))
      (node (ref "R5") (pin "1") (pinfunction "1_1") (pintype "passive"))
      (node (ref "R7") (pin "1") (pinfunction "1_1") (pintype "passive"))
      (node (ref "R8") (pin "2") (pinfunction "2_2") (pintype "passive"))
      (node (ref "U1") (pin "14") (pinfunction "O_14") (pintype "passive"))
    )
    (net (code "70") (name "Net-(U6-EN)") (class "Default")
      (node (ref "R50") (pin "2") (pinfunction "2_2") (pintype "passive"))
      (node (ref "R52") (pin "2") (pinfunction "2_2") (pintype "passive"))
      (node (ref "U6") (pin "4") (pinfunction "EN_4") (pintype "passive"))
    )
    (net (code "71") (name "Net-(U6-FB)") (class "Default")
      (node (ref "C34") (pin "1") (pinfunction "1_1") (pintype "passive"))
      (node (ref "R48") (pin "1") (pinfunction "1_1") (pintype "passive"))
      (node (ref "R51") (pin "1") (pinfunction "1_1") (pintype "passive"))
      (node (ref "U6") (pin "3") (pinfunction "FB_3") (pintype "passive"))
    )
    (net (code "72") (name "SWD") (class "Default")
      (node (ref "J2") (pin "4") (pinfunction "4_4") (pintype "passive"))
      (node (ref "U4") (pin "23") (pinfunction "PA13_23") (pintype "passive"))
    )
    (net (code "73") (name "USB5V") (class "Default")
      (node (ref "C20") (pin "2") (pinfunction "2_2") (pintype "passive"))
      (node (ref "C27") (pin "2") (pinfunction "2_2") (pintype "passive"))
      (node (ref "C28") (pin "2") (pinfunction "2_2") (pintype "passive"))
      (node (ref "C37") (pin "2") (pinfunction "2_2") (pintype "passive"))
      (node (ref "C4") (pin "2") (pinfunction "2_2") (pintype "passive"))
      (node (ref "L10") (pin "1") (pinfunction "1_1") (pintype "passive"))
      (node (ref "L2") (pin "3") (pinfunction "A_3") (pintype "passive"))
      (node (ref "L2") (pin "4") (pinfunction "A_4") (pintype "passive"))
      (node (ref "M1") (pin "2") (pinfunction "D1_2") (pintype "passive"))
      (node (ref "M1") (pin "3") (pinfunction "D1_3") (pintype "passive"))
      (node (ref "M1") (pin "4") (pinfunction "D1_4") (pintype "passive"))
      (node (ref "M2") (pin "2") (pinfunction "D1_2") (pintype "passive"))
      (node (ref "M2") (pin "3") (pinfunction "D1_3") (pintype "passive"))
      (node (ref "M2") (pin "4") (pinfunction "D1_4") (pintype "passive"))
      (node (ref "R30") (pin "2") (pinfunction "2_2") (pintype "passive"))
      (node (ref "R39") (pin "2") (pinfunction "2_2") (pintype "passive"))
      (node (ref "R40") (pin "2") (pinfunction "2_2") (pintype "passive"))
      (node (ref "R41") (pin "2") (pinfunction "2_2") (pintype "passive"))
      (node (ref "R42") (pin "2") (pinfunction "2_2") (pintype "passive"))
      (node (ref "R43") (pin "2") (pinfunction "2_2") (pintype "passive"))
      (node (ref "R44") (pin "2") (pinfunction "2_2") (pintype "passive"))
      (node (ref "R45") (pin "2") (pinfunction "2_2") (pintype "passive"))
      (node (ref "R50") (pin "1") (pinfunction "1_1") (pintype "passive"))
      (node (ref "T9") (pin "1") (pinfunction "1_1") (pintype "passive"))
      (node (ref "U6") (pin "5") (pinfunction "VCC_5") (pintype "passive"))
      (node (ref "USB1") (pin "1") (pinfunction "1_1") (pintype "passive"))
    )
    (net (code "74") (name "unconnected-(U4-PA2-Pad8)") (class "Default")
      (node (ref "U4") (pin "8") (pinfunction "PA2_8") (pintype "passive+no_connect"))
    )
    (net (code "75") (name "unconnected-(U4-PA11-Pad21)") (class "Default")
      (node (ref "U4") (pin "21") (pinfunction "PA11_21") (pintype "passive+no_connect"))
    )
    (net (code "76") (name "unconnected-(U4-PA12-Pad22)") (class "Default")
      (node (ref "U4") (pin "22") (pinfunction "PA12_22") (pintype "passive+no_connect"))
    )
    (net (code "77") (name "unconnected-(U4-PC0-Pad2)") (class "Default")
      (node (ref "U4") (pin "2") (pinfunction "PC0_2") (pintype "passive+no_connect"))
    )
    (net (code "78") (name "unconnected-(U4-PC1-Pad3)") (class "Default")
      (node (ref "U4") (pin "3") (pinfunction "PC1_3") (pintype "passive+no_connect"))
    )
    (net (code "79") (name "unconnected-(U6-OC-Pad6)") (class "Default")
      (node (ref "U6") (pin "6") (pinfunction "OC_6") (pintype "passive+no_connect"))
    )
  )
)
